# PowerSupply.net
KiCad netlist of a schematic drawn in Altium Designer
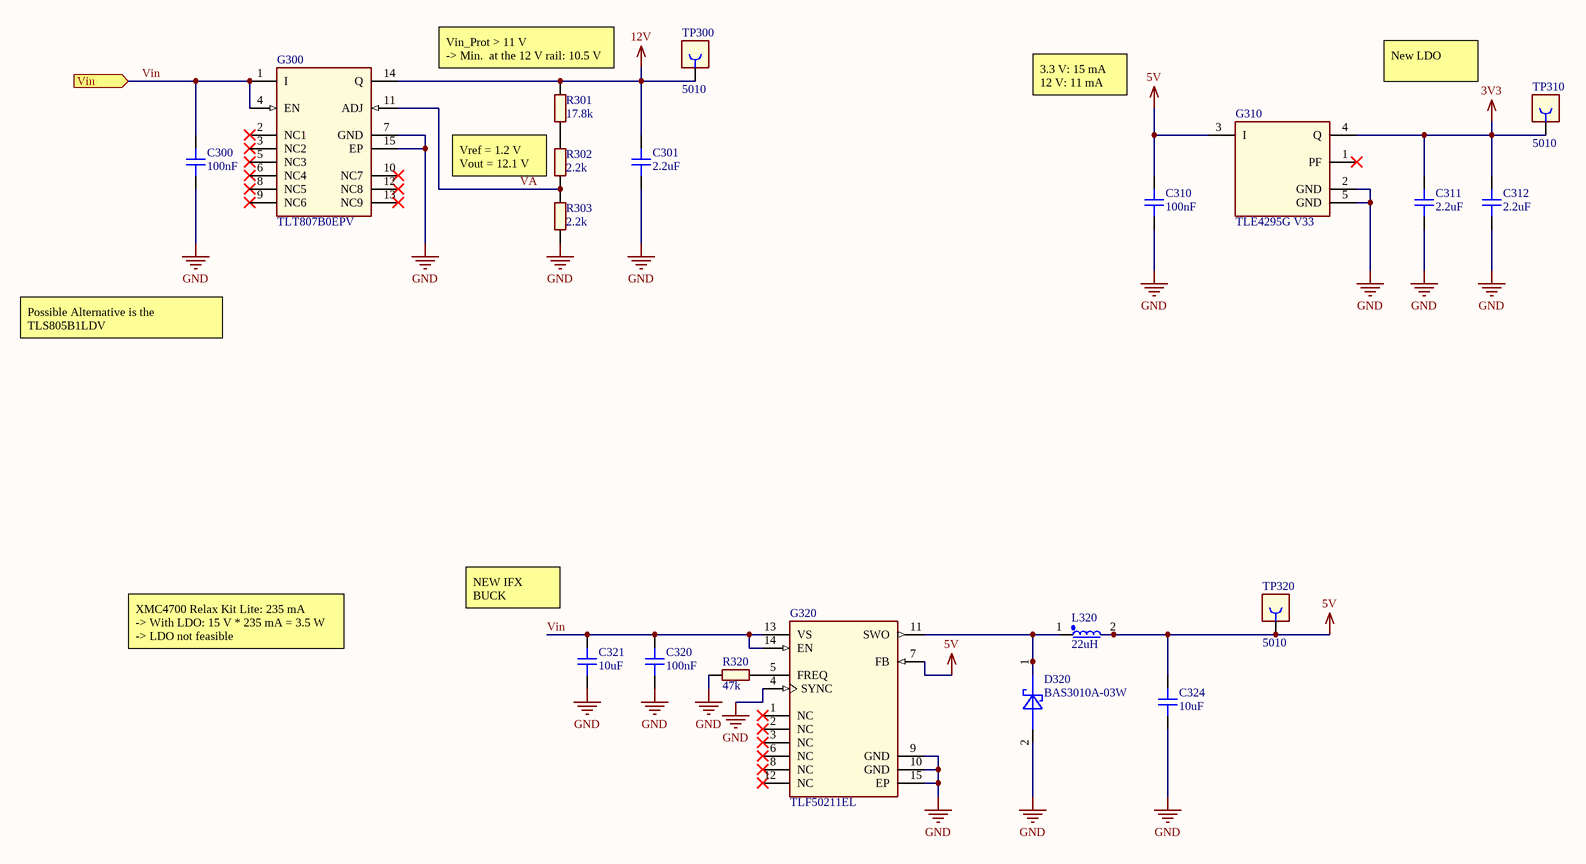
[diagram p0: PowerSupply.SchDoc]

(export (version "E")
  (design (tool "Eeschema 10.0.6"))
  (components
    (comp (ref "C300")
      (value "100nF")
      (footprint "CAPC3216X125N-0")
      (description "CAP / CERA / 100nF / 50V / 10% / X7R (EIA) / -55°C to 125°C / 1206(3216) / SMD / -")
      (fields (field (name "LEGACY PARTNUMBER") "CAP01005660") (field (name "MANUFACTURER") "MuRata"))
      (libsource (lib "PCBLibraryData") (part "CAP-SGL-STD-02P_00000001"))
    )
    (comp (ref "C301")
      (value "2.2uF")
      (footprint "CAPC3216X70N")
      (description "CAP / CERA / 2.2uF / 25V / 10% / X5R (EIA) / -55°C to 85°C / 1206(3216) / SMD / -")
      (fields (field (name "LEGACY PARTNUMBER") "CAP01005015") (field (name "MANUFACTURER") "MuRata"))
      (libsource (lib "PCBLibraryData") (part "CAP-SGL-STD-02P_00000001"))
    )
    (comp (ref "C310")
      (value "100nF")
      (footprint "CAPC3216X125N-0")
      (description "CAP / CERA / 100nF / 50V / 10% / X7R (EIA) / -55°C to 125°C / 1206(3216) / SMD / -")
      (fields (field (name "LEGACY PARTNUMBER") "CAP01005660") (field (name "MANUFACTURER") "MuRata"))
      (libsource (lib "PCBLibraryData") (part "CAP-SGL-STD-02P_00000001"))
    )
    (comp (ref "C311")
      (value "2.2uF")
      (footprint "CAPC3216X70N")
      (description "CAP / CERA / 2.2uF / 25V / 10% / X5R (EIA) / -55°C to 85°C / 1206(3216) / SMD / -")
      (fields (field (name "LEGACY PARTNUMBER") "CAP01005015") (field (name "MANUFACTURER") "MuRata"))
      (libsource (lib "PCBLibraryData") (part "CAP-SGL-STD-02P_00000001"))
    )
    (comp (ref "C312")
      (value "2.2uF")
      (footprint "CAPC3216X70N")
      (description "CAP / CERA / 2.2uF / 25V / 10% / X5R (EIA) / -55°C to 85°C / 1206(3216) / SMD / -")
      (fields (field (name "LEGACY PARTNUMBER") "CAP01005015") (field (name "MANUFACTURER") "MuRata"))
      (libsource (lib "PCBLibraryData") (part "CAP-SGL-STD-02P_00000001"))
    )
    (comp (ref "C320")
      (value "100nF")
      (footprint "CAPC3216X125N-0")
      (description "CAP / CERA / 100nF / 50V / 10% / X7R (EIA) / -55°C to 125°C / 1206(3216) / SMD / -")
      (fields (field (name "LEGACY PARTNUMBER") "CAP01005660") (field (name "MANUFACTURER") "MuRata"))
      (libsource (lib "PCBLibraryData") (part "CAP-SGL-STD-02P_00000001"))
    )
    (comp (ref "C321")
      (value "10uF")
      (footprint "CAPC3216X190N-1")
      (description "CAP / CERA / 10uF / 50V / 20% / X5R (EIA) / -55°C to 85°C / 1206 (3216) / SMD / -")
      (fields (field (name "MANUFACTURER") "Taiyo Yuden"))
      (libsource (lib "PCBLibraryData") (part "CAP-SGL-STD-02P_00000001"))
    )
    (comp (ref "C324")
      (value "10uF")
      (footprint "CAPC3216X190N-1")
      (description "CAP / CERA / 10uF / 50V / 20% / X5R (EIA) / -55°C to 85°C / 1206 (3216) / SMD / -")
      (fields (field (name "MANUFACTURER") "Taiyo Yuden"))
      (libsource (lib "PCBLibraryData") (part "CAP-SGL-STD-02P_00000001"))
    )
    (comp (ref "D320")
      (value "BAS3010A-03W")
      (footprint "SOD2513X110N")
      (description "Medium Power AF Schottky Diode")
      (fields
        (field (name "LEGACY PARTNUMBER") "IFX01400145")
        (field (name "MANUFACTURER") "Infineon Technologies")
      )
      (libsource (lib "PCBLibraryData") (part "d_schottky_a"))
    )
    (comp (ref "G300")
      (value "TLT807B0EPV")
      (footprint "SOP65P600X115-15N")
      (description "Low Dropout Adjustable Standby Voltage Regulator")
      (fields
        (field (name "LEGACY PARTNUMBER") "IFX01401452")
        (field (name "MANUFACTURER") "Infineon Technologies")
      )
      (libsource (lib "PCBLibraryData") (part "TLT807B0EPV"))
    )
    (comp (ref "G310")
      (value "TLE4295G V33")
      (footprint "IFX-PG-SCT595-5-2")
      (fields (field (name "MANUFACTURER") "Infineon Technologies"))
      (libsource (lib "PCBLibraryData") (part "TLE4285 G"))
    )
    (comp (ref "G320")
      (value "TLF50211EL")
      (footprint "SOP65P600X170-15N")
      (description "2.2 MHz Step-Down Regulator 500 mA, 5 V, low quiescent current")
      (fields (field (name "MANUFACTURER") "Infineon Technologies"))
      (libsource (lib "PCBLibraryData") (part "IFX90121EL"))
    )
    (comp (ref "L320")
      (value "22uH")
      (footprint "IND-SMD-74404064220")
      (fields (field (name "MANUFACTURER") "Wurth Elektronik"))
      (libsource (lib "PCBLibraryData") (part "IND-SGL-STD-WDG-COR-02P_0000002B"))
    )
    (comp (ref "R301")
      (value "17.8k")
      (footprint "RESC3216X60N")
      (description "RES / STD / 17.8k / 250mW / 1% / 100ppm/K / -55°C to 155°C / 1206(3216) / SMD / -")
      (fields (field (name "LEGACY PARTNUMBER") "RES01802883") (field (name "MANUFACTURER") "Vishay"))
      (libsource (lib "") (part "RES-SGL-STD-02P_00000006_2"))
    )
    (comp (ref "R302")
      (value "2.2k")
      (footprint "RESC3216X60N")
      (description "RES / STD / 2.2k / 250mW / 1% / 100ppm/K / -55°C to 155°C / 1206(3216) / SMD / -")
      (fields (field (name "LEGACY PARTNUMBER") "RES01802779") (field (name "MANUFACTURER") "Vishay"))
      (libsource (lib "") (part "RES-SGL-STD-02P_00000006_1"))
    )
    (comp (ref "R303")
      (value "2.2k")
      (footprint "RESC3216X60N")
      (description "RES / STD / 2.2k / 250mW / 1% / 100ppm/K / -55°C to 155°C / 1206(3216) / SMD / -")
      (fields (field (name "LEGACY PARTNUMBER") "RES01802779") (field (name "MANUFACTURER") "Vishay"))
      (libsource (lib "") (part "RES-SGL-STD-02P_00000006_1"))
    )
    (comp (ref "R320")
      (value "47k")
      (footprint "RESC3216X60N")
      (description "RES / STD / 47k / 250mW / 1% / 100ppm/K / -55°C to 155°C / 1206(3216) / SMD / -")
      (fields (field (name "LEGACY PARTNUMBER") "RES01802933") (field (name "MANUFACTURER") "Vishay"))
      (libsource (lib "PCBLibraryData") (part "RES-SGL-STD-02P_00000006"))
    )
    (comp (ref "TP300")
      (value "5010")
      (footprint "CON-THT-TP-5010")
      (description "PC Test Point-Multipurpose THT, Red")
      (fields
        (field (name "LEGACY PARTNUMBER") "CON01500529")
        (field (name "MANUFACTURER") "Keystone Electronics Corp.")
      )
      (libsource (lib "PCBLibraryData") (part "connector_1_f"))
    )
    (comp (ref "TP310")
      (value "5010")
      (footprint "CON-THT-TP-5010")
      (description "PC Test Point-Multipurpose THT, Red")
      (fields
        (field (name "LEGACY PARTNUMBER") "CON01500529")
        (field (name "MANUFACTURER") "Keystone Electronics Corp.")
      )
      (libsource (lib "PCBLibraryData") (part "connector_1_f"))
    )
    (comp (ref "TP320")
      (value "5010")
      (footprint "CON-THT-TP-5010")
      (description "PC Test Point-Multipurpose THT, Red")
      (fields
        (field (name "LEGACY PARTNUMBER") "CON01500529")
        (field (name "MANUFACTURER") "Keystone Electronics Corp.")
      )
      (libsource (lib "PCBLibraryData") (part "connector_1_f"))
    )
  )
  (nets
    (net (code "1") (name "/VA") (class "Default")
      (node (ref "G300") (pin "11") (pinfunction "ADJ_11") (pintype "input"))
      (node (ref "R302") (pin "1") (pinfunction "1_1") (pintype "passive"))
      (node (ref "R303") (pin "2") (pinfunction "2_2") (pintype "passive"))
    )
    (net (code "2") (name "/Vin") (class "Default")
      (node (ref "C300") (pin "2") (pinfunction "2_2") (pintype "passive"))
      (node (ref "C320") (pin "2") (pinfunction "2_2") (pintype "passive"))
      (node (ref "C321") (pin "2") (pinfunction "2_2") (pintype "passive"))
      (node (ref "G300") (pin "1") (pinfunction "I_1") (pintype "power_in"))
      (node (ref "G300") (pin "4") (pinfunction "EN_4") (pintype "input"))
      (node (ref "G320") (pin "13") (pinfunction "VS_13") (pintype "power_in"))
      (node (ref "G320") (pin "14") (pinfunction "EN_14") (pintype "input"))
    )
    (net (code "3") (name "3V3") (class "Default")
      (node (ref "C311") (pin "2") (pinfunction "2_2") (pintype "passive"))
      (node (ref "C312") (pin "2") (pinfunction "2_2") (pintype "passive"))
      (node (ref "G310") (pin "4") (pinfunction "Q_4") (pintype "power_in"))
      (node (ref "TP310") (pin "1") (pinfunction "1_1") (pintype "passive"))
    )
    (net (code "4") (name "5V") (class "Default")
      (node (ref "C310") (pin "2") (pinfunction "2_2") (pintype "passive"))
      (node (ref "C324") (pin "2") (pinfunction "2_2") (pintype "passive"))
      (node (ref "G310") (pin "3") (pinfunction "I_3") (pintype "power_in"))
      (node (ref "G320") (pin "7") (pinfunction "FB_7") (pintype "input"))
      (node (ref "L320") (pin "2") (pinfunction "2_2") (pintype "passive"))
      (node (ref "TP320") (pin "1") (pinfunction "1_1") (pintype "passive"))
    )
    (net (code "5") (name "12V") (class "Default")
      (node (ref "C301") (pin "2") (pinfunction "2_2") (pintype "passive"))
      (node (ref "G300") (pin "14") (pinfunction "Q_14") (pintype "power_in"))
      (node (ref "R301") (pin "1") (pinfunction "1_1") (pintype "passive"))
      (node (ref "TP300") (pin "1") (pinfunction "1_1") (pintype "passive"))
    )
    (net (code "6") (name "GND") (class "Default")
      (node (ref "C300") (pin "1") (pinfunction "1_1") (pintype "passive"))
      (node (ref "C301") (pin "1") (pinfunction "1_1") (pintype "passive"))
      (node (ref "C310") (pin "1") (pinfunction "1_1") (pintype "passive"))
      (node (ref "C311") (pin "1") (pinfunction "1_1") (pintype "passive"))
      (node (ref "C312") (pin "1") (pinfunction "1_1") (pintype "passive"))
      (node (ref "C320") (pin "1") (pinfunction "1_1") (pintype "passive"))
      (node (ref "C321") (pin "1") (pinfunction "1_1") (pintype "passive"))
      (node (ref "C324") (pin "1") (pinfunction "1_1") (pintype "passive"))
      (node (ref "D320") (pin "2") (pinfunction "Anode_2") (pintype "passive"))
      (node (ref "G300") (pin "15") (pinfunction "EP_15") (pintype "power_in"))
      (node (ref "G300") (pin "7") (pinfunction "GND_7") (pintype "power_in"))
      (node (ref "G310") (pin "2") (pinfunction "GND_2") (pintype "power_in"))
      (node (ref "G310") (pin "5") (pinfunction "GND_5") (pintype "power_in"))
      (node (ref "G320") (pin "10") (pinfunction "GND_10") (pintype "power_in"))
      (node (ref "G320") (pin "15") (pinfunction "EP_15") (pintype "power_in"))
      (node (ref "G320") (pin "4") (pinfunction "SYNC_4") (pintype "input"))
      (node (ref "G320") (pin "9") (pinfunction "GND_9") (pintype "power_in"))
      (node (ref "R303") (pin "1") (pinfunction "1_1") (pintype "passive"))
      (node (ref "R320") (pin "2") (pinfunction "2_2") (pintype "passive"))
    )
    (net (code "7") (name "Net-(D320-Cathode)") (class "Default")
      (node (ref "D320") (pin "1") (pinfunction "Cathode_1") (pintype "passive"))
      (node (ref "G320") (pin "11") (pinfunction "SWO_11") (pintype "output"))
      (node (ref "L320") (pin "1") (pinfunction "1_1") (pintype "passive"))
    )
    (net (code "8") (name "Net-(G320-FREQ)") (class "Default")
      (node (ref "G320") (pin "5") (pinfunction "FREQ_5") (pintype "passive"))
      (node (ref "R320") (pin "1") (pinfunction "1_1") (pintype "passive"))
    )
    (net (code "9") (name "Net-(R301-Pad2)") (class "Default")
      (node (ref "R301") (pin "2") (pinfunction "2_2") (pintype "passive"))
      (node (ref "R302") (pin "2") (pinfunction "2_2") (pintype "passive"))
    )
    (net (code "10") (name "unconnected-(G300-NC1-Pad2)") (class "Default")
      (node (ref "G300") (pin "2") (pinfunction "NC1_2") (pintype "passive+no_connect"))
    )
    (net (code "11") (name "unconnected-(G300-NC2-Pad3)") (class "Default")
      (node (ref "G300") (pin "3") (pinfunction "NC2_3") (pintype "passive+no_connect"))
    )
    (net (code "12") (name "unconnected-(G300-NC3-Pad5)") (class "Default")
      (node (ref "G300") (pin "5") (pinfunction "NC3_5") (pintype "passive+no_connect"))
    )
    (net (code "13") (name "unconnected-(G300-NC4-Pad6)") (class "Default")
      (node (ref "G300") (pin "6") (pinfunction "NC4_6") (pintype "passive+no_connect"))
    )
    (net (code "14") (name "unconnected-(G300-NC5-Pad8)") (class "Default")
      (node (ref "G300") (pin "8") (pinfunction "NC5_8") (pintype "passive+no_connect"))
    )
    (net (code "15") (name "unconnected-(G300-NC6-Pad9)") (class "Default")
      (node (ref "G300") (pin "9") (pinfunction "NC6_9") (pintype "passive+no_connect"))
    )
    (net (code "16") (name "unconnected-(G300-NC7-Pad10)") (class "Default")
      (node (ref "G300") (pin "10") (pinfunction "NC7_10") (pintype "passive+no_connect"))
    )
    (net (code "17") (name "unconnected-(G300-NC8-Pad12)") (class "Default")
      (node (ref "G300") (pin "12") (pinfunction "NC8_12") (pintype "passive+no_connect"))
    )
    (net (code "18") (name "unconnected-(G300-NC9-Pad13)") (class "Default")
      (node (ref "G300") (pin "13") (pinfunction "NC9_13") (pintype "passive+no_connect"))
    )
    (net (code "19") (name "unconnected-(G310-PF-Pad1)") (class "Default")
      (node (ref "G310") (pin "1") (pinfunction "PF_1") (pintype "power_in+no_connect"))
    )
    (net (code "20") (name "unconnected-(G320-NC-Pad1)") (class "Default")
      (node (ref "G320") (pin "1") (pinfunction "NC_1") (pintype "passive+no_connect"))
    )
    (net (code "21") (name "unconnected-(G320-NC-Pad2)") (class "Default")
      (node (ref "G320") (pin "2") (pinfunction "NC_2") (pintype "passive+no_connect"))
    )
    (net (code "22") (name "unconnected-(G320-NC-Pad3)") (class "Default")
      (node (ref "G320") (pin "3") (pinfunction "NC_3") (pintype "passive+no_connect"))
    )
    (net (code "23") (name "unconnected-(G320-NC-Pad6)") (class "Default")
      (node (ref "G320") (pin "6") (pinfunction "NC_6") (pintype "passive+no_connect"))
    )
    (net (code "24") (name "unconnected-(G320-NC-Pad8)") (class "Default")
      (node (ref "G320") (pin "8") (pinfunction "NC_8") (pintype "passive+no_connect"))
    )
    (net (code "25") (name "unconnected-(G320-NC-Pad12)") (class "Default")
      (node (ref "G320") (pin "12") (pinfunction "NC_12") (pintype "passive+no_connect"))
    )
  )
)
